# USBasp.net
KiCad netlist of a schematic drawn in EAGLE
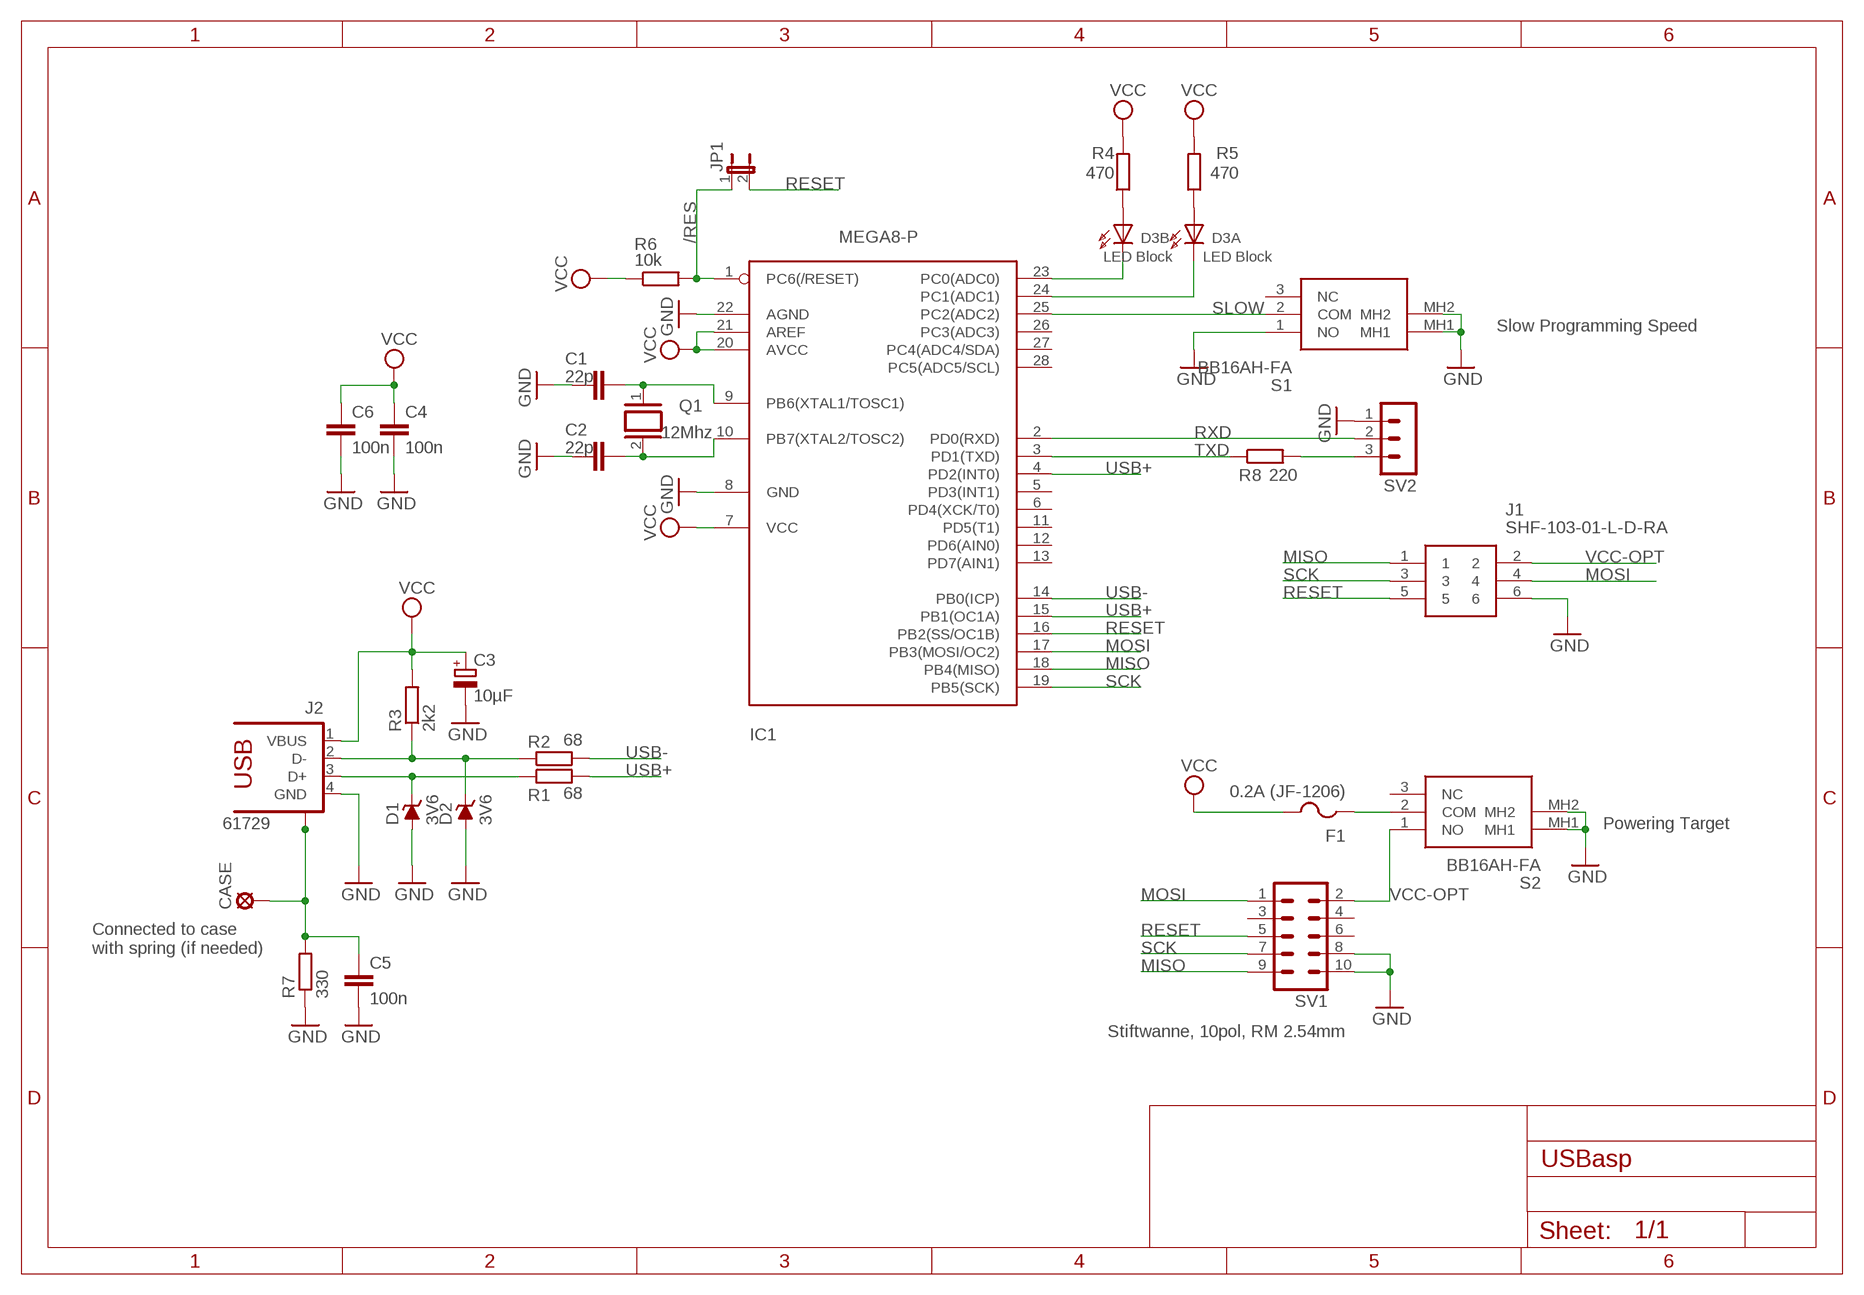
[diagram p0: schematic, sheet 1]

(export (version "E")
  (design (tool "Eeschema 10.0.6"))
  (components
    (comp (ref "C1")
      (value "22p")
      (footprint "eagle-import:C025-024X044")
      (libsource (lib "eagle-import") (part "C-EU025-024X044"))
    )
    (comp (ref "C2")
      (value "22p")
      (footprint "eagle-import:C025-024X044")
      (libsource (lib "eagle-import") (part "C-EU025-024X044"))
    )
    (comp (ref "C3")
      (value "10µF")
      (footprint "eagle-import:E2,5-6")
      (libsource (lib "eagle-import") (part "CPOL-EUE2.5-6"))
    )
    (comp (ref "C4")
      (value "100n")
      (footprint "eagle-import:C050-024X044")
      (libsource (lib "eagle-import") (part "C-EU050-024X044"))
    )
    (comp (ref "C5")
      (value "100n")
      (footprint "eagle-import:C050-024X044")
      (libsource (lib "eagle-import") (part "C-EU050-024X044"))
    )
    (comp (ref "C6")
      (value "100n")
      (footprint "eagle-import:C050-024X044")
      (libsource (lib "eagle-import") (part "C-EU050-024X044"))
    )
    (comp (ref "CASE")
      (value "LSP10")
      (footprint "eagle-import:LSP10")
      (libsource (lib "eagle-import") (part "LSP10"))
    )
    (comp (ref "D1")
      (value "3V6")
      (footprint "eagle-import:DO35Z10")
      (libsource (lib "eagle-import") (part "BZX55"))
    )
    (comp (ref "D2")
      (value "3V6")
      (footprint "eagle-import:DO35Z10")
      (libsource (lib "eagle-import") (part "BZX55"))
    )
    (comp (ref "D3")
      (value "LED Block")
      (footprint "eagle-import:1801_PINS_SWAPPED")
      (libsource (lib "eagle-import") (part "1801_PINS_SWAPPED"))
    )
    (comp (ref "F1")
      (value "0.2A (JF-1206)")
      (footprint "eagle-import:R1206")
      (libsource (lib "eagle-import") (part "PTCFUSE-1206"))
    )
    (comp (ref "IC1")
      (value "MEGA8-P")
      (footprint "eagle-import:DIL28-3")
      (libsource (lib "eagle-import") (part "MEGA8-P"))
    )
    (comp (ref "J1")
      (value "SHF-103-01-L-D-RA")
      (footprint "eagle-import:SHF10301LDRA")
      (libsource (lib "eagle-import") (part "SHF-103-01-L-D-RA"))
    )
    (comp (ref "J2")
      (value "61729")
      (footprint "eagle-import:61729")
      (libsource (lib "eagle-import") (part "61729"))
    )
    (comp (ref "JP1")
      (value "JP1E")
      (footprint "eagle-import:JP1")
      (libsource (lib "eagle-import") (part "JP1E"))
    )
    (comp (ref "Q1")
      (value "12Mhz")
      (footprint "eagle-import:QS")
      (libsource (lib "eagle-import") (part "XTAL/S"))
    )
    (comp (ref "R1")
      (value "68")
      (footprint "eagle-import:0207_10")
      (libsource (lib "eagle-import") (part "R-EU_0207/10"))
    )
    (comp (ref "R2")
      (value "68")
      (footprint "eagle-import:0207_10")
      (libsource (lib "eagle-import") (part "R-EU_0207/10"))
    )
    (comp (ref "R3")
      (value "2k2")
      (footprint "eagle-import:0207_10")
      (libsource (lib "eagle-import") (part "R-EU_0207/10"))
    )
    (comp (ref "R4")
      (value "470")
      (footprint "eagle-import:0207_10")
      (libsource (lib "eagle-import") (part "R-EU_0207/10"))
    )
    (comp (ref "R5")
      (value "470")
      (footprint "eagle-import:0207_10")
      (libsource (lib "eagle-import") (part "R-EU_0207/10"))
    )
    (comp (ref "R6")
      (value "10k")
      (footprint "eagle-import:0207_10")
      (libsource (lib "eagle-import") (part "R-EU_0207/10"))
    )
    (comp (ref "R7")
      (value "330")
      (footprint "eagle-import:0207_10")
      (libsource (lib "eagle-import") (part "R-EU_0207/10"))
    )
    (comp (ref "R8")
      (value "220")
      (footprint "eagle-import:R0805")
      (libsource (lib "eagle-import") (part "R-EU_R0805"))
    )
    (comp (ref "S1")
      (value "BB16AH-FA")
      (footprint "eagle-import:BB16AHFA")
      (fields (field (name "MOUSER_PART_NUMBER") "633-BB16AH-FA"))
      (libsource (lib "eagle-import") (part "BB16AH-FA"))
    )
    (comp (ref "S2")
      (value "BB16AH-FA")
      (footprint "eagle-import:BB16AHFA")
      (fields (field (name "MOUSER_PART_NUMBER") "633-BB16AH-FA"))
      (libsource (lib "eagle-import") (part "BB16AH-FA"))
    )
    (comp (ref "SV1")
      (value "Stiftwanne, 10pol, RM 2.54mm")
      (footprint "eagle-import:ML10L")
      (libsource (lib "eagle-import") (part "ML10L"))
    )
    (comp (ref "SV2")
      (value "MA03-1")
      (footprint "eagle-import:MA03-1")
      (libsource (lib "eagle-import") (part "MA03-1"))
    )
  )
  (nets
    (net (code "1") (name "/MISO") (class "Default")
      (node (ref "IC1") (pin "18") (pinfunction "PB4(MISO)_18") (pintype "bidirectional"))
      (node (ref "J1") (pin "1") (pinfunction "1_1") (pintype "bidirectional"))
      (node (ref "SV1") (pin "9") (pinfunction "9_9") (pintype "passive"))
    )
    (net (code "2") (name "/MOSI") (class "Default")
      (node (ref "IC1") (pin "17") (pinfunction "PB3(MOSI/OC2)_17") (pintype "bidirectional"))
      (node (ref "J1") (pin "4") (pinfunction "4_4") (pintype "bidirectional"))
      (node (ref "SV1") (pin "1") (pinfunction "1_1") (pintype "passive"))
    )
    (net (code "3") (name "/RESET") (class "Default")
      (node (ref "IC1") (pin "16") (pinfunction "PB2(SS/OC1B)_16") (pintype "bidirectional"))
      (node (ref "J1") (pin "5") (pinfunction "5_5") (pintype "bidirectional"))
      (node (ref "JP1") (pin "2") (pinfunction "2_2") (pintype "passive"))
      (node (ref "SV1") (pin "5") (pinfunction "5_5") (pintype "passive"))
    )
    (net (code "4") (name "/RXD") (class "Default")
      (node (ref "IC1") (pin "2") (pinfunction "PD0(RXD)_2") (pintype "bidirectional"))
      (node (ref "SV2") (pin "2") (pinfunction "2_2") (pintype "passive"))
    )
    (net (code "5") (name "/SCK") (class "Default")
      (node (ref "IC1") (pin "19") (pinfunction "PB5(SCK)_19") (pintype "bidirectional"))
      (node (ref "J1") (pin "3") (pinfunction "3_3") (pintype "bidirectional"))
      (node (ref "SV1") (pin "7") (pinfunction "7_7") (pintype "passive"))
    )
    (net (code "6") (name "/SLOW") (class "Default")
      (node (ref "IC1") (pin "25") (pinfunction "PC2(ADC2)_25") (pintype "bidirectional"))
      (node (ref "S1") (pin "2") (pinfunction "COM_2") (pintype "bidirectional"))
    )
    (net (code "7") (name "/TXD") (class "Default")
      (node (ref "IC1") (pin "3") (pinfunction "PD1(TXD)_3") (pintype "bidirectional"))
      (node (ref "R8") (pin "1") (pinfunction "1_1") (pintype "passive"))
    )
    (net (code "8") (name "/USB+") (class "Default")
      (node (ref "IC1") (pin "15") (pinfunction "PB1(OC1A)_15") (pintype "bidirectional"))
      (node (ref "IC1") (pin "4") (pinfunction "PD2(INT0)_4") (pintype "bidirectional"))
      (node (ref "R1") (pin "2") (pinfunction "2_2") (pintype "passive"))
    )
    (net (code "9") (name "/USB-") (class "Default")
      (node (ref "IC1") (pin "14") (pinfunction "PB0(ICP)_14") (pintype "bidirectional"))
      (node (ref "R2") (pin "2") (pinfunction "2_2") (pintype "passive"))
    )
    (net (code "10") (name "/VCC-OPT") (class "Default")
      (node (ref "J1") (pin "2") (pinfunction "2_2") (pintype "bidirectional"))
      (node (ref "S2") (pin "1") (pinfunction "NO_1") (pintype "bidirectional"))
      (node (ref "SV1") (pin "2") (pinfunction "2_2") (pintype "passive"))
    )
    (net (code "11") (name "/{slash}RES") (class "Default")
      (node (ref "IC1") (pin "1") (pinfunction "PC6(/RESET)_1") (pintype "bidirectional"))
      (node (ref "JP1") (pin "1") (pinfunction "1_1") (pintype "passive"))
      (node (ref "R6") (pin "2") (pinfunction "2_2") (pintype "passive"))
    )
    (net (code "12") (name "GND") (class "Default")
      (node (ref "C1") (pin "1") (pinfunction "1_1") (pintype "passive"))
      (node (ref "C2") (pin "1") (pinfunction "1_1") (pintype "passive"))
      (node (ref "C3") (pin "-") (pinfunction "-_-") (pintype "passive"))
      (node (ref "C4") (pin "2") (pinfunction "2_2") (pintype "passive"))
      (node (ref "C5") (pin "2") (pinfunction "2_2") (pintype "passive"))
      (node (ref "C6") (pin "2") (pinfunction "2_2") (pintype "passive"))
      (node (ref "D1") (pin "A") (pinfunction "A_A") (pintype "passive"))
      (node (ref "D2") (pin "A") (pinfunction "A_A") (pintype "passive"))
      (node (ref "IC1") (pin "22") (pinfunction "AGND_22") (pintype "bidirectional"))
      (node (ref "IC1") (pin "8") (pinfunction "GND_8") (pintype "bidirectional"))
      (node (ref "J1") (pin "6") (pinfunction "6_6") (pintype "bidirectional"))
      (node (ref "J2") (pin "4") (pinfunction "GND_4") (pintype "passive"))
      (node (ref "R7") (pin "1") (pinfunction "1_1") (pintype "passive"))
      (node (ref "S1") (pin "1") (pinfunction "NO_1") (pintype "bidirectional"))
      (node (ref "S1") (pin "MH1") (pinfunction "MH1_MH1") (pintype "bidirectional"))
      (node (ref "S1") (pin "MH2") (pinfunction "MH2_MH2") (pintype "bidirectional"))
      (node (ref "S2") (pin "MH1") (pinfunction "MH1_MH1") (pintype "bidirectional"))
      (node (ref "S2") (pin "MH2") (pinfunction "MH2_MH2") (pintype "bidirectional"))
      (node (ref "SV1") (pin "10") (pinfunction "10_10") (pintype "passive"))
      (node (ref "SV1") (pin "8") (pinfunction "8_8") (pintype "passive"))
      (node (ref "SV2") (pin "1") (pinfunction "1_1") (pintype "passive"))
    )
    (net (code "13") (name "Net-(C5-Pad1)") (class "Default")
      (node (ref "C5") (pin "1") (pinfunction "1_1") (pintype "passive"))
      (node (ref "CASE") (pin "MP") (pinfunction "MP_MP") (pintype "passive"))
      (node (ref "J2") (pin "S1") (pinfunction "S1_S1") (pintype "passive"))
      (node (ref "J2") (pin "S2") (pinfunction "S2_S2") (pintype "passive"))
      (node (ref "R7") (pin "2") (pinfunction "2_2") (pintype "passive"))
    )
    (net (code "14") (name "Net-(D3-PadA)") (class "Default")
      (node (ref "D3") (pin "A") (pinfunction "A_A") (pintype "passive"))
      (node (ref "R5") (pin "1") (pinfunction "1_1") (pintype "passive"))
    )
    (net (code "15") (name "Net-(D3B-A)") (class "Default")
      (node (ref "D3") (pin "A1") (pinfunction "A_A1") (pintype "passive"))
      (node (ref "R4") (pin "1") (pinfunction "1_1") (pintype "passive"))
    )
    (net (code "16") (name "Net-(D3B-K)") (class "Default")
      (node (ref "D3") (pin "K1") (pinfunction "K_K1") (pintype "passive"))
      (node (ref "IC1") (pin "23") (pinfunction "PC0(ADC0)_23") (pintype "bidirectional"))
    )
    (net (code "17") (name "Net-(IC1-PB6(XTAL1{slash}TOSC1))") (class "Default")
      (node (ref "C1") (pin "2") (pinfunction "2_2") (pintype "passive"))
      (node (ref "IC1") (pin "9") (pinfunction "PB6(XTAL1/TOSC1)_9") (pintype "bidirectional"))
      (node (ref "Q1") (pin "1") (pinfunction "1_1") (pintype "passive"))
    )
    (net (code "18") (name "Net-(IC1-PB7(XTAL2{slash}TOSC2))") (class "Default")
      (node (ref "C2") (pin "2") (pinfunction "2_2") (pintype "passive"))
      (node (ref "IC1") (pin "10") (pinfunction "PB7(XTAL2/TOSC2)_10") (pintype "bidirectional"))
      (node (ref "Q1") (pin "2") (pinfunction "2_2") (pintype "passive"))
    )
    (net (code "19") (name "Net-(IC1-PC1(ADC1))") (class "Default")
      (node (ref "D3") (pin "K") (pinfunction "K_K") (pintype "passive"))
      (node (ref "IC1") (pin "24") (pinfunction "PC1(ADC1)_24") (pintype "bidirectional"))
    )
    (net (code "20") (name "Net-(J2-D+)") (class "Default")
      (node (ref "D1") (pin "C") (pinfunction "C_C") (pintype "passive"))
      (node (ref "J2") (pin "3") (pinfunction "D+_3") (pintype "passive"))
      (node (ref "R1") (pin "1") (pinfunction "1_1") (pintype "passive"))
    )
    (net (code "21") (name "Net-(J2-D-)") (class "Default")
      (node (ref "D2") (pin "C") (pinfunction "C_C") (pintype "passive"))
      (node (ref "J2") (pin "2") (pinfunction "D-_2") (pintype "passive"))
      (node (ref "R2") (pin "1") (pinfunction "1_1") (pintype "passive"))
      (node (ref "R3") (pin "1") (pinfunction "1_1") (pintype "passive"))
    )
    (net (code "22") (name "Net-(R8-Pad2)") (class "Default")
      (node (ref "R8") (pin "2") (pinfunction "2_2") (pintype "passive"))
      (node (ref "SV2") (pin "3") (pinfunction "3_3") (pintype "passive"))
    )
    (net (code "23") (name "Net-(S2-COM)") (class "Default")
      (node (ref "F1") (pin "1") (pinfunction "1_1") (pintype "passive"))
      (node (ref "S2") (pin "2") (pinfunction "COM_2") (pintype "bidirectional"))
    )
    (net (code "24") (name "VCC") (class "Default")
      (node (ref "C3") (pin "+") (pinfunction "+_+") (pintype "passive"))
      (node (ref "C4") (pin "1") (pinfunction "1_1") (pintype "passive"))
      (node (ref "C6") (pin "1") (pinfunction "1_1") (pintype "passive"))
      (node (ref "F1") (pin "2") (pinfunction "2_2") (pintype "passive"))
      (node (ref "IC1") (pin "20") (pinfunction "AVCC_20") (pintype "bidirectional"))
      (node (ref "IC1") (pin "21") (pinfunction "AREF_21") (pintype "bidirectional"))
      (node (ref "IC1") (pin "7") (pinfunction "VCC_7") (pintype "bidirectional"))
      (node (ref "J2") (pin "1") (pinfunction "VBUS_1") (pintype "passive"))
      (node (ref "R3") (pin "2") (pinfunction "2_2") (pintype "passive"))
      (node (ref "R4") (pin "2") (pinfunction "2_2") (pintype "passive"))
      (node (ref "R5") (pin "2") (pinfunction "2_2") (pintype "passive"))
      (node (ref "R6") (pin "1") (pinfunction "1_1") (pintype "passive"))
    )
    (net (code "25") (name "unconnected-(IC1-PC3(ADC3)-Pad26)") (class "Default")
      (node (ref "IC1") (pin "26") (pinfunction "PC3(ADC3)_26") (pintype "bidirectional"))
    )
    (net (code "26") (name "unconnected-(IC1-PC4(ADC4{slash}SDA)-Pad27)") (class "Default")
      (node (ref "IC1") (pin "27") (pinfunction "PC4(ADC4/SDA)_27") (pintype "bidirectional"))
    )
    (net (code "27") (name "unconnected-(IC1-PC5(ADC5{slash}SCL)-Pad28)") (class "Default")
      (node (ref "IC1") (pin "28") (pinfunction "PC5(ADC5/SCL)_28") (pintype "bidirectional"))
    )
    (net (code "28") (name "unconnected-(IC1-PD3(INT1)-Pad5)") (class "Default")
      (node (ref "IC1") (pin "5") (pinfunction "PD3(INT1)_5") (pintype "bidirectional"))
    )
    (net (code "29") (name "unconnected-(IC1-PD4(XCK{slash}T0)-Pad6)") (class "Default")
      (node (ref "IC1") (pin "6") (pinfunction "PD4(XCK/T0)_6") (pintype "bidirectional"))
    )
    (net (code "30") (name "unconnected-(IC1-PD5(T1)-Pad11)") (class "Default")
      (node (ref "IC1") (pin "11") (pinfunction "PD5(T1)_11") (pintype "bidirectional"))
    )
    (net (code "31") (name "unconnected-(IC1-PD6(AIN0)-Pad12)") (class "Default")
      (node (ref "IC1") (pin "12") (pinfunction "PD6(AIN0)_12") (pintype "bidirectional"))
    )
    (net (code "32") (name "unconnected-(IC1-PD7(AIN1)-Pad13)") (class "Default")
      (node (ref "IC1") (pin "13") (pinfunction "PD7(AIN1)_13") (pintype "bidirectional"))
    )
    (net (code "33") (name "unconnected-(S1-NC-Pad3)") (class "Default")
      (node (ref "S1") (pin "3") (pinfunction "NC_3") (pintype "no_connect"))
    )
    (net (code "34") (name "unconnected-(S2-NC-Pad3)") (class "Default")
      (node (ref "S2") (pin "3") (pinfunction "NC_3") (pintype "no_connect"))
    )
    (net (code "35") (name "unconnected-(SV1-Pad3)") (class "Default")
      (node (ref "SV1") (pin "3") (pinfunction "3_3") (pintype "passive"))
    )
    (net (code "36") (name "unconnected-(SV1-Pad4)") (class "Default")
      (node (ref "SV1") (pin "4") (pinfunction "4_4") (pintype "passive"))
    )
    (net (code "37") (name "unconnected-(SV1-Pad6)") (class "Default")
      (node (ref "SV1") (pin "6") (pinfunction "6_6") (pintype "passive"))
    )
  )
)
